# deska_vyrobena.net
KiCad netlist of a schematic drawn in EAGLE
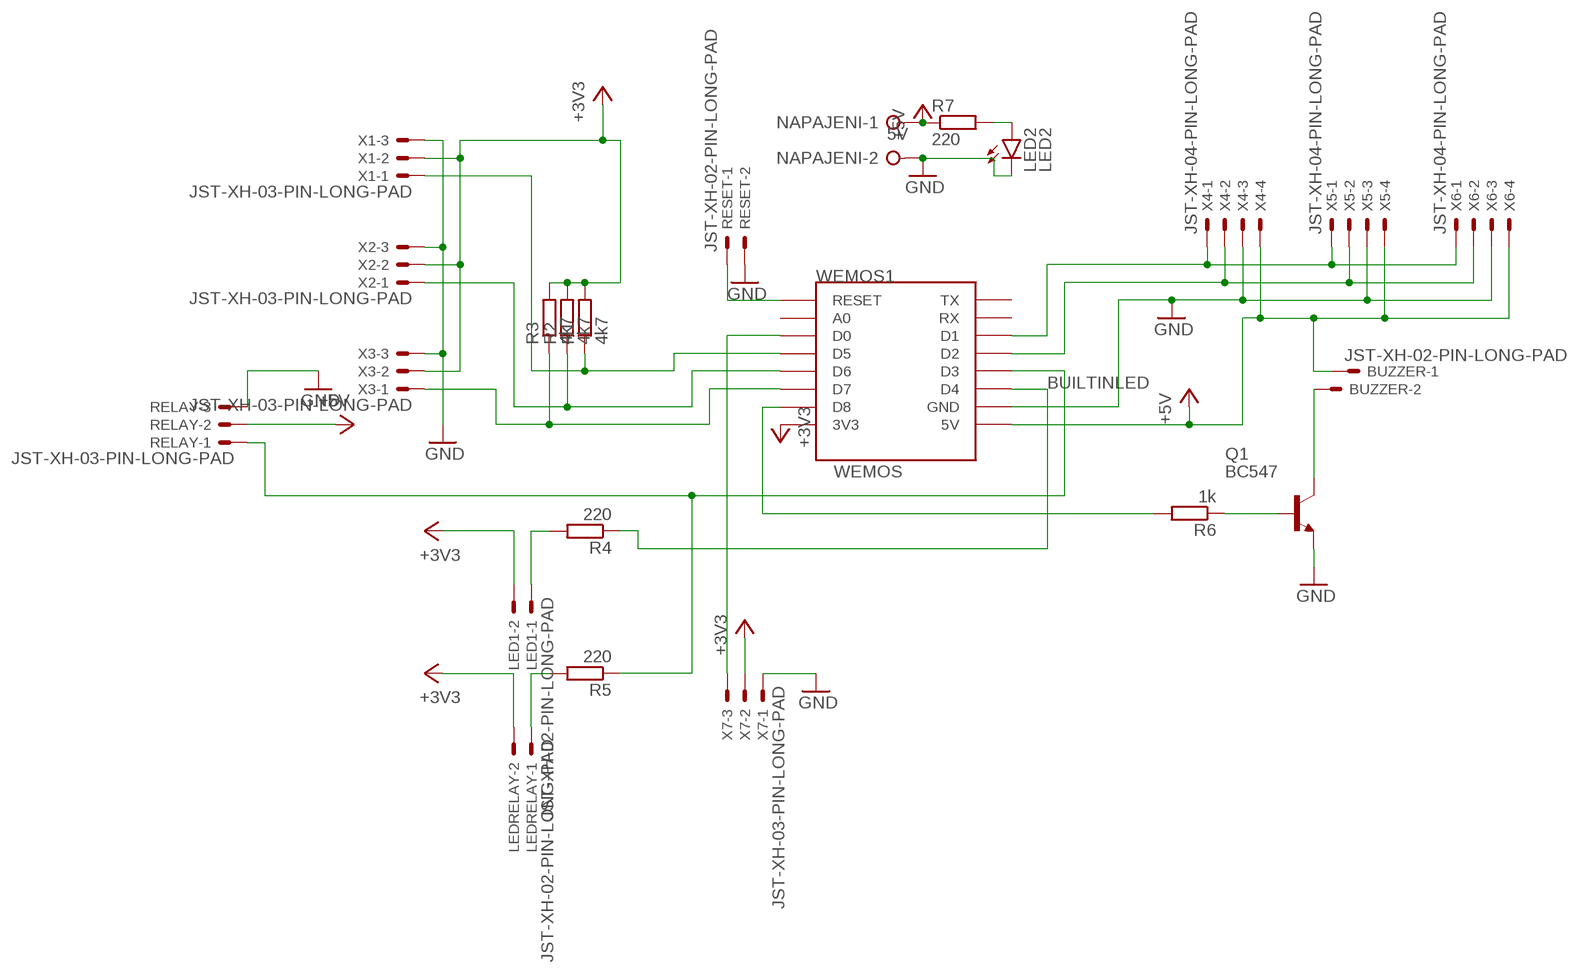
[diagram p0: schematic, sheet 1]

(export (version "E")
  (design (tool "Eeschema 10.0.6"))
  (components
    (comp (ref "BUZZER")
      (value "JST-XH-02-PIN-LONG-PAD")
      (footprint "eagle-import:JST-XH-02-PACKAGE-LONG-PAD")
      (libsource (lib "eagle-import") (part "JST-XH-02-PIN-LONG-PAD"))
    )
    (comp (ref "LED1")
      (value "JST-XH-02-PIN-LONG-PAD")
      (footprint "eagle-import:JST-XH-02-PACKAGE-LONG-PAD")
      (libsource (lib "eagle-import") (part "JST-XH-02-PIN-LONG-PAD"))
    )
    (comp (ref "LED2")
      (value "LED2")
      (footprint "eagle-import:LED3MM")
      (libsource (lib "eagle-import") (part "LED3MM"))
    )
    (comp (ref "LEDRELAY")
      (value "JST-XH-02-PIN-LONG-PAD")
      (footprint "eagle-import:JST-XH-02-PACKAGE-LONG-PAD")
      (libsource (lib "eagle-import") (part "JST-XH-02-PIN-LONG-PAD"))
    )
    (comp (ref "NAPAJENI")
      (value "5V")
      (footprint "eagle-import:W237-132")
      (libsource (lib "eagle-import") (part "W237-02P"))
    )
    (comp (ref "Q1")
      (value "BC547")
      (footprint "eagle-import:TO92")
      (libsource (lib "eagle-import") (part "BC547"))
    )
    (comp (ref "R1")
      (value "4k7")
      (footprint "eagle-import:0207_7")
      (libsource (lib "eagle-import") (part "R-EU_0207/7"))
    )
    (comp (ref "R2")
      (value "4k7")
      (footprint "eagle-import:0207_7")
      (libsource (lib "eagle-import") (part "R-EU_0207/7"))
    )
    (comp (ref "R3")
      (value "4k7")
      (footprint "eagle-import:0207_7")
      (libsource (lib "eagle-import") (part "R-EU_0207/7"))
    )
    (comp (ref "R4")
      (value "220")
      (footprint "eagle-import:0207_7")
      (libsource (lib "eagle-import") (part "R-EU_0207/7"))
    )
    (comp (ref "R5")
      (value "220")
      (footprint "eagle-import:0207_7")
      (libsource (lib "eagle-import") (part "R-EU_0207/7"))
    )
    (comp (ref "R6")
      (value "1k")
      (footprint "eagle-import:0207_7")
      (libsource (lib "eagle-import") (part "R-EU_0207/7"))
    )
    (comp (ref "R7")
      (value "220")
      (footprint "eagle-import:0207_7")
      (libsource (lib "eagle-import") (part "R-EU_0207/7"))
    )
    (comp (ref "RELAY")
      (value "JST-XH-03-PIN-LONG-PAD")
      (footprint "eagle-import:JST-XH-03-PACKAGE-LONG-PAD")
      (libsource (lib "eagle-import") (part "JST-XH-03-PIN-LONG-PAD"))
    )
    (comp (ref "RESET")
      (value "JST-XH-02-PIN-LONG-PAD")
      (footprint "eagle-import:JST-XH-02-PACKAGE-LONG-PAD")
      (libsource (lib "eagle-import") (part "JST-XH-02-PIN-LONG-PAD"))
    )
    (comp (ref "WEMOS1")
      (value "WEMOS")
      (footprint "eagle-import:WEMOS-D1-MINI")
      (libsource (lib "eagle-import") (part "WEMOS-D1-MINI"))
    )
    (comp (ref "X1")
      (value "JST-XH-03-PIN-LONG-PAD")
      (footprint "eagle-import:JST-XH-03-PACKAGE-LONG-PAD")
      (libsource (lib "eagle-import") (part "JST-XH-03-PIN-LONG-PAD"))
    )
    (comp (ref "X2")
      (value "JST-XH-03-PIN-LONG-PAD")
      (footprint "eagle-import:JST-XH-03-PACKAGE-LONG-PAD")
      (libsource (lib "eagle-import") (part "JST-XH-03-PIN-LONG-PAD"))
    )
    (comp (ref "X3")
      (value "JST-XH-03-PIN-LONG-PAD")
      (footprint "eagle-import:JST-XH-03-PACKAGE-LONG-PAD")
      (libsource (lib "eagle-import") (part "JST-XH-03-PIN-LONG-PAD"))
    )
    (comp (ref "X4")
      (value "JST-XH-04-PIN-LONG-PAD")
      (footprint "eagle-import:JST-XH-04-PACKAGE-LONG-PAD")
      (libsource (lib "eagle-import") (part "JST-XH-04-PIN-LONG-PAD"))
    )
    (comp (ref "X5")
      (value "JST-XH-04-PIN-LONG-PAD")
      (footprint "eagle-import:JST-XH-04-PACKAGE-LONG-PAD")
      (libsource (lib "eagle-import") (part "JST-XH-04-PIN-LONG-PAD"))
    )
    (comp (ref "X6")
      (value "JST-XH-04-PIN-LONG-PAD")
      (footprint "eagle-import:JST-XH-04-PACKAGE-LONG-PAD")
      (libsource (lib "eagle-import") (part "JST-XH-04-PIN-LONG-PAD"))
    )
    (comp (ref "X7")
      (value "JST-XH-03-PIN-LONG-PAD")
      (footprint "eagle-import:JST-XH-03-PACKAGE-LONG-PAD")
      (libsource (lib "eagle-import") (part "JST-XH-03-PIN-LONG-PAD"))
    )
  )
  (nets
    (net (code "1") (name "+3V3") (class "Default")
      (node (ref "LED1") (pin "2") (pinfunction "S_2") (pintype "passive"))
      (node (ref "LEDRELAY") (pin "2") (pinfunction "S_2") (pintype "passive"))
      (node (ref "R1") (pin "2") (pinfunction "2_2") (pintype "passive"))
      (node (ref "R2") (pin "2") (pinfunction "2_2") (pintype "passive"))
      (node (ref "R3") (pin "2") (pinfunction "2_2") (pintype "passive"))
      (node (ref "WEMOS1") (pin "3V3") (pinfunction "3V3_3V3") (pintype "bidirectional"))
      (node (ref "X1") (pin "2") (pinfunction "S_2") (pintype "passive"))
      (node (ref "X2") (pin "2") (pinfunction "S_2") (pintype "passive"))
      (node (ref "X3") (pin "2") (pinfunction "S_2") (pintype "passive"))
      (node (ref "X7") (pin "2") (pinfunction "S_2") (pintype "passive"))
    )
    (net (code "2") (name "+5V") (class "Default")
      (node (ref "BUZZER") (pin "1") (pinfunction "S_1") (pintype "passive"))
      (node (ref "NAPAJENI") (pin "1") (pinfunction "KL_1") (pintype "passive"))
      (node (ref "R7") (pin "1") (pinfunction "1_1") (pintype "passive"))
      (node (ref "RELAY") (pin "2") (pinfunction "S_2") (pintype "passive"))
      (node (ref "WEMOS1") (pin "5V") (pinfunction "5V_5V") (pintype "bidirectional"))
      (node (ref "X4") (pin "4") (pinfunction "S_4") (pintype "passive"))
      (node (ref "X5") (pin "4") (pinfunction "S_4") (pintype "passive"))
      (node (ref "X6") (pin "4") (pinfunction "S_4") (pintype "passive"))
    )
    (net (code "3") (name "/BUILTINLED") (class "Default")
      (node (ref "R4") (pin "1") (pinfunction "1_1") (pintype "passive"))
      (node (ref "WEMOS1") (pin "D4") (pinfunction "D4_D4") (pintype "bidirectional"))
    )
    (net (code "4") (name "GND") (class "Default")
      (node (ref "LED2") (pin "K") (pinfunction "C_K") (pintype "passive"))
      (node (ref "NAPAJENI") (pin "2") (pinfunction "KL_2") (pintype "passive"))
      (node (ref "Q1") (pin "1") (pinfunction "E_1") (pintype "passive"))
      (node (ref "RELAY") (pin "3") (pinfunction "S_3") (pintype "passive"))
      (node (ref "RESET") (pin "2") (pinfunction "S_2") (pintype "passive"))
      (node (ref "WEMOS1") (pin "GND") (pinfunction "GND_GND") (pintype "bidirectional"))
      (node (ref "X1") (pin "3") (pinfunction "S_3") (pintype "passive"))
      (node (ref "X2") (pin "3") (pinfunction "S_3") (pintype "passive"))
      (node (ref "X3") (pin "3") (pinfunction "S_3") (pintype "passive"))
      (node (ref "X4") (pin "3") (pinfunction "S_3") (pintype "passive"))
      (node (ref "X5") (pin "3") (pinfunction "S_3") (pintype "passive"))
      (node (ref "X6") (pin "3") (pinfunction "S_3") (pintype "passive"))
      (node (ref "X7") (pin "1") (pinfunction "S_1") (pintype "passive"))
    )
    (net (code "5") (name "Net-(BUZZERB-S)") (class "Default")
      (node (ref "BUZZER") (pin "2") (pinfunction "S_2") (pintype "passive"))
      (node (ref "Q1") (pin "3") (pinfunction "C_3") (pintype "passive"))
    )
    (net (code "6") (name "Net-(LED1A-S)") (class "Default")
      (node (ref "LED1") (pin "1") (pinfunction "S_1") (pintype "passive"))
      (node (ref "R4") (pin "2") (pinfunction "2_2") (pintype "passive"))
    )
    (net (code "7") (name "Net-(LED2-PadA)") (class "Default")
      (node (ref "LED2") (pin "A") (pinfunction "A_A") (pintype "passive"))
      (node (ref "R7") (pin "2") (pinfunction "2_2") (pintype "passive"))
    )
    (net (code "8") (name "Net-(LEDRELAYA-S)") (class "Default")
      (node (ref "LEDRELAY") (pin "1") (pinfunction "S_1") (pintype "passive"))
      (node (ref "R5") (pin "2") (pinfunction "2_2") (pintype "passive"))
    )
    (net (code "9") (name "Net-(Q1-B)") (class "Default")
      (node (ref "Q1") (pin "2") (pinfunction "B_2") (pintype "passive"))
      (node (ref "R6") (pin "1") (pinfunction "1_1") (pintype "passive"))
    )
    (net (code "10") (name "Net-(R6-Pad2)") (class "Default")
      (node (ref "R6") (pin "2") (pinfunction "2_2") (pintype "passive"))
      (node (ref "WEMOS1") (pin "D8") (pinfunction "D8_D8") (pintype "bidirectional"))
    )
    (net (code "11") (name "Net-(RELAYA-S)") (class "Default")
      (node (ref "R5") (pin "1") (pinfunction "1_1") (pintype "passive"))
      (node (ref "RELAY") (pin "1") (pinfunction "S_1") (pintype "passive"))
      (node (ref "WEMOS1") (pin "D3") (pinfunction "D3_D3") (pintype "bidirectional"))
    )
    (net (code "12") (name "Net-(RESETA-S)") (class "Default")
      (node (ref "RESET") (pin "1") (pinfunction "S_1") (pintype "passive"))
      (node (ref "WEMOS1") (pin "RESET") (pinfunction "RESET_RESET") (pintype "bidirectional"))
    )
    (net (code "13") (name "Net-(X1A-S)") (class "Default")
      (node (ref "R1") (pin "1") (pinfunction "1_1") (pintype "passive"))
      (node (ref "WEMOS1") (pin "D5") (pinfunction "D5_D5") (pintype "bidirectional"))
      (node (ref "X1") (pin "1") (pinfunction "S_1") (pintype "passive"))
    )
    (net (code "14") (name "Net-(X2A-S)") (class "Default")
      (node (ref "R2") (pin "1") (pinfunction "1_1") (pintype "passive"))
      (node (ref "WEMOS1") (pin "D6") (pinfunction "D6_D6") (pintype "bidirectional"))
      (node (ref "X2") (pin "1") (pinfunction "S_1") (pintype "passive"))
    )
    (net (code "15") (name "Net-(X3A-S)") (class "Default")
      (node (ref "R3") (pin "1") (pinfunction "1_1") (pintype "passive"))
      (node (ref "WEMOS1") (pin "D7") (pinfunction "D7_D7") (pintype "bidirectional"))
      (node (ref "X3") (pin "1") (pinfunction "S_1") (pintype "passive"))
    )
    (net (code "16") (name "Net-(X4A-S)") (class "Default")
      (node (ref "WEMOS1") (pin "D1") (pinfunction "D1_D1") (pintype "bidirectional"))
      (node (ref "X4") (pin "1") (pinfunction "S_1") (pintype "passive"))
      (node (ref "X5") (pin "1") (pinfunction "S_1") (pintype "passive"))
      (node (ref "X6") (pin "1") (pinfunction "S_1") (pintype "passive"))
    )
    (net (code "17") (name "Net-(X4B-S)") (class "Default")
      (node (ref "WEMOS1") (pin "D2") (pinfunction "D2_D2") (pintype "bidirectional"))
      (node (ref "X4") (pin "2") (pinfunction "S_2") (pintype "passive"))
      (node (ref "X5") (pin "2") (pinfunction "S_2") (pintype "passive"))
      (node (ref "X6") (pin "2") (pinfunction "S_2") (pintype "passive"))
    )
    (net (code "18") (name "Net-(X7C-S)") (class "Default")
      (node (ref "WEMOS1") (pin "D0") (pinfunction "D0_D0") (pintype "bidirectional"))
      (node (ref "X7") (pin "3") (pinfunction "S_3") (pintype "passive"))
    )
    (net (code "19") (name "unconnected-(WEMOS1-PadA0)") (class "Default")
      (node (ref "WEMOS1") (pin "A0") (pinfunction "A0_A0") (pintype "bidirectional"))
    )
    (net (code "20") (name "unconnected-(WEMOS1-PadRX)") (class "Default")
      (node (ref "WEMOS1") (pin "RX") (pinfunction "RX_RX") (pintype "bidirectional"))
    )
    (net (code "21") (name "unconnected-(WEMOS1-PadTX)") (class "Default")
      (node (ref "WEMOS1") (pin "TX") (pinfunction "TX_TX") (pintype "bidirectional"))
    )
  )
)
